# Digital_Port_A_Default_State_DIP.net
KiCad netlist of a schematic drawn in Altium Designer
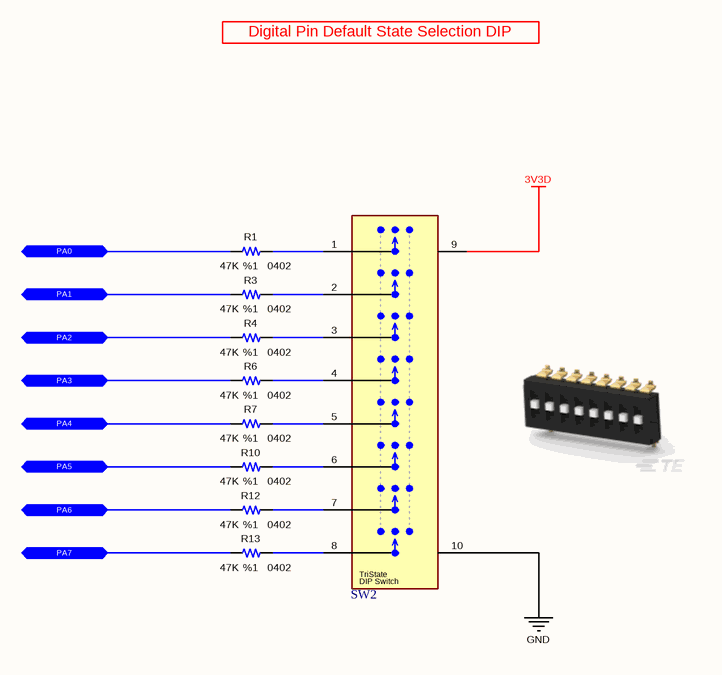
[diagram p0: Digital Port A Default State DIP.SchDoc]

(export (version "E")
  (design (tool "Eeschema 10.0.6"))
  (components
    (comp (ref "R1")
      (value "47K")
      (footprint "RESISTOR_0402")
      (description "Thick Film Resistors - SMD 1/16 W 47 Kohms 1%")
      (fields
        (field (name "MANUFACTURER PART NUMBER") "CRCW040247K0FKED")
        (field (name "MOUSER PART NUMBER") "71-CRCW0402-47K-E3")
        (field (name "TOLERANCE") "%1")
        (field (name "CASE") "0402")
      )
      (libsource (lib "Ovoo_Library") (part "Resistor - 47K"))
    )
    (comp (ref "R3")
      (value "47K")
      (footprint "RESISTOR_0402")
      (description "Thick Film Resistors - SMD 1/16 W 47 Kohms 1%")
      (fields
        (field (name "MANUFACTURER PART NUMBER") "CRCW040247K0FKED")
        (field (name "MOUSER PART NUMBER") "71-CRCW0402-47K-E3")
        (field (name "TOLERANCE") "%1")
        (field (name "CASE") "0402")
      )
      (libsource (lib "Ovoo_Library") (part "Resistor - 47K"))
    )
    (comp (ref "R4")
      (value "47K")
      (footprint "RESISTOR_0402")
      (description "Thick Film Resistors - SMD 1/16 W 47 Kohms 1%")
      (fields
        (field (name "MANUFACTURER PART NUMBER") "CRCW040247K0FKED")
        (field (name "MOUSER PART NUMBER") "71-CRCW0402-47K-E3")
        (field (name "TOLERANCE") "%1")
        (field (name "CASE") "0402")
      )
      (libsource (lib "Ovoo_Library") (part "Resistor - 47K"))
    )
    (comp (ref "R6")
      (value "47K")
      (footprint "RESISTOR_0402")
      (description "Thick Film Resistors - SMD 1/16 W 47 Kohms 1%")
      (fields
        (field (name "MANUFACTURER PART NUMBER") "CRCW040247K0FKED")
        (field (name "MOUSER PART NUMBER") "71-CRCW0402-47K-E3")
        (field (name "TOLERANCE") "%1")
        (field (name "CASE") "0402")
      )
      (libsource (lib "Ovoo_Library") (part "Resistor - 47K"))
    )
    (comp (ref "R7")
      (value "47K")
      (footprint "RESISTOR_0402")
      (description "Thick Film Resistors - SMD 1/16 W 47 Kohms 1%")
      (fields
        (field (name "MANUFACTURER PART NUMBER") "CRCW040247K0FKED")
        (field (name "MOUSER PART NUMBER") "71-CRCW0402-47K-E3")
        (field (name "TOLERANCE") "%1")
        (field (name "CASE") "0402")
      )
      (libsource (lib "Ovoo_Library") (part "Resistor - 47K"))
    )
    (comp (ref "R10")
      (value "47K")
      (footprint "RESISTOR_0402")
      (description "Thick Film Resistors - SMD 1/16 W 47 Kohms 1%")
      (fields
        (field (name "MANUFACTURER PART NUMBER") "CRCW040247K0FKED")
        (field (name "MOUSER PART NUMBER") "71-CRCW0402-47K-E3")
        (field (name "TOLERANCE") "%1")
        (field (name "CASE") "0402")
      )
      (libsource (lib "Ovoo_Library") (part "Resistor - 47K"))
    )
    (comp (ref "R12")
      (value "47K")
      (footprint "RESISTOR_0402")
      (description "Thick Film Resistors - SMD 1/16 W 47 Kohms 1%")
      (fields
        (field (name "MANUFACTURER PART NUMBER") "CRCW040247K0FKED")
        (field (name "MOUSER PART NUMBER") "71-CRCW0402-47K-E3")
        (field (name "TOLERANCE") "%1")
        (field (name "CASE") "0402")
      )
      (libsource (lib "Ovoo_Library") (part "Resistor - 47K"))
    )
    (comp (ref "R13")
      (value "47K")
      (footprint "RESISTOR_0402")
      (description "Thick Film Resistors - SMD 1/16 W 47 Kohms 1%")
      (fields
        (field (name "MANUFACTURER PART NUMBER") "CRCW040247K0FKED")
        (field (name "MOUSER PART NUMBER") "71-CRCW0402-47K-E3")
        (field (name "TOLERANCE") "%1")
        (field (name "CASE") "0402")
      )
      (libsource (lib "Ovoo_Library") (part "Resistor - 47K"))
    )
    (comp (ref "SW2")
      (value "DIP Switches/SIP Switches")
      (footprint "TDS08SGNNTR04")
      (description "DIP Switches/SIP Switches TRI-STATE DIP 8P G RAISED T&R")
      (fields
        (field (name "MANUFACTURER PART NUMBER") "TDS08SGNNTR04")
        (field (name "MOUSER PART NUMBER") "506-TDS08SGNNTR04")
      )
      (libsource (lib "Ovoo_Library") (part "Switch - DIP Switch (8 Pole TriState)"))
    )
  )
  (nets
    (net (code "1") (name "/PA0") (class "Default")
      (node (ref "R1") (pin "2") (pinfunction "2_2") (pintype "passive"))
    )
    (net (code "2") (name "/PA1") (class "Default")
      (node (ref "R3") (pin "2") (pinfunction "2_2") (pintype "passive"))
    )
    (net (code "3") (name "/PA2") (class "Default")
      (node (ref "R4") (pin "2") (pinfunction "2_2") (pintype "passive"))
    )
    (net (code "4") (name "/PA3") (class "Default")
      (node (ref "R6") (pin "2") (pinfunction "2_2") (pintype "passive"))
    )
    (net (code "5") (name "/PA4") (class "Default")
      (node (ref "R7") (pin "2") (pinfunction "2_2") (pintype "passive"))
    )
    (net (code "6") (name "/PA5") (class "Default")
      (node (ref "R10") (pin "2") (pinfunction "2_2") (pintype "passive"))
    )
    (net (code "7") (name "/PA6") (class "Default")
      (node (ref "R12") (pin "2") (pinfunction "2_2") (pintype "passive"))
    )
    (net (code "8") (name "/PA7") (class "Default")
      (node (ref "R13") (pin "2") (pinfunction "2_2") (pintype "passive"))
    )
    (net (code "9") (name "3V3D") (class "Default")
      (node (ref "SW2") (pin "9") (pinfunction "VCC_9") (pintype "passive"))
    )
    (net (code "10") (name "GND") (class "Default")
      (node (ref "SW2") (pin "10") (pinfunction "GND_10") (pintype "passive"))
    )
    (net (code "11") (name "Net-(R1-Pad1)") (class "Default")
      (node (ref "R1") (pin "1") (pinfunction "1_1") (pintype "passive"))
      (node (ref "SW2") (pin "1") (pinfunction "1_1") (pintype "passive"))
    )
    (net (code "12") (name "Net-(R3-Pad1)") (class "Default")
      (node (ref "R3") (pin "1") (pinfunction "1_1") (pintype "passive"))
      (node (ref "SW2") (pin "2") (pinfunction "2_2") (pintype "passive"))
    )
    (net (code "13") (name "Net-(R4-Pad1)") (class "Default")
      (node (ref "R4") (pin "1") (pinfunction "1_1") (pintype "passive"))
      (node (ref "SW2") (pin "3") (pinfunction "3_3") (pintype "passive"))
    )
    (net (code "14") (name "Net-(R6-Pad1)") (class "Default")
      (node (ref "R6") (pin "1") (pinfunction "1_1") (pintype "passive"))
      (node (ref "SW2") (pin "4") (pinfunction "4_4") (pintype "passive"))
    )
    (net (code "15") (name "Net-(R7-Pad1)") (class "Default")
      (node (ref "R7") (pin "1") (pinfunction "1_1") (pintype "passive"))
      (node (ref "SW2") (pin "5") (pinfunction "5_5") (pintype "passive"))
    )
    (net (code "16") (name "Net-(R10-Pad1)") (class "Default")
      (node (ref "R10") (pin "1") (pinfunction "1_1") (pintype "passive"))
      (node (ref "SW2") (pin "6") (pinfunction "6_6") (pintype "passive"))
    )
    (net (code "17") (name "Net-(R12-Pad1)") (class "Default")
      (node (ref "R12") (pin "1") (pinfunction "1_1") (pintype "passive"))
      (node (ref "SW2") (pin "7") (pinfunction "7_7") (pintype "passive"))
    )
    (net (code "18") (name "Net-(R13-Pad1)") (class "Default")
      (node (ref "R13") (pin "1") (pinfunction "1_1") (pintype "passive"))
      (node (ref "SW2") (pin "8") (pinfunction "8_8") (pintype "passive"))
    )
  )
)
